# Sheet3.net
KiCad netlist of a schematic drawn in Altium Designer
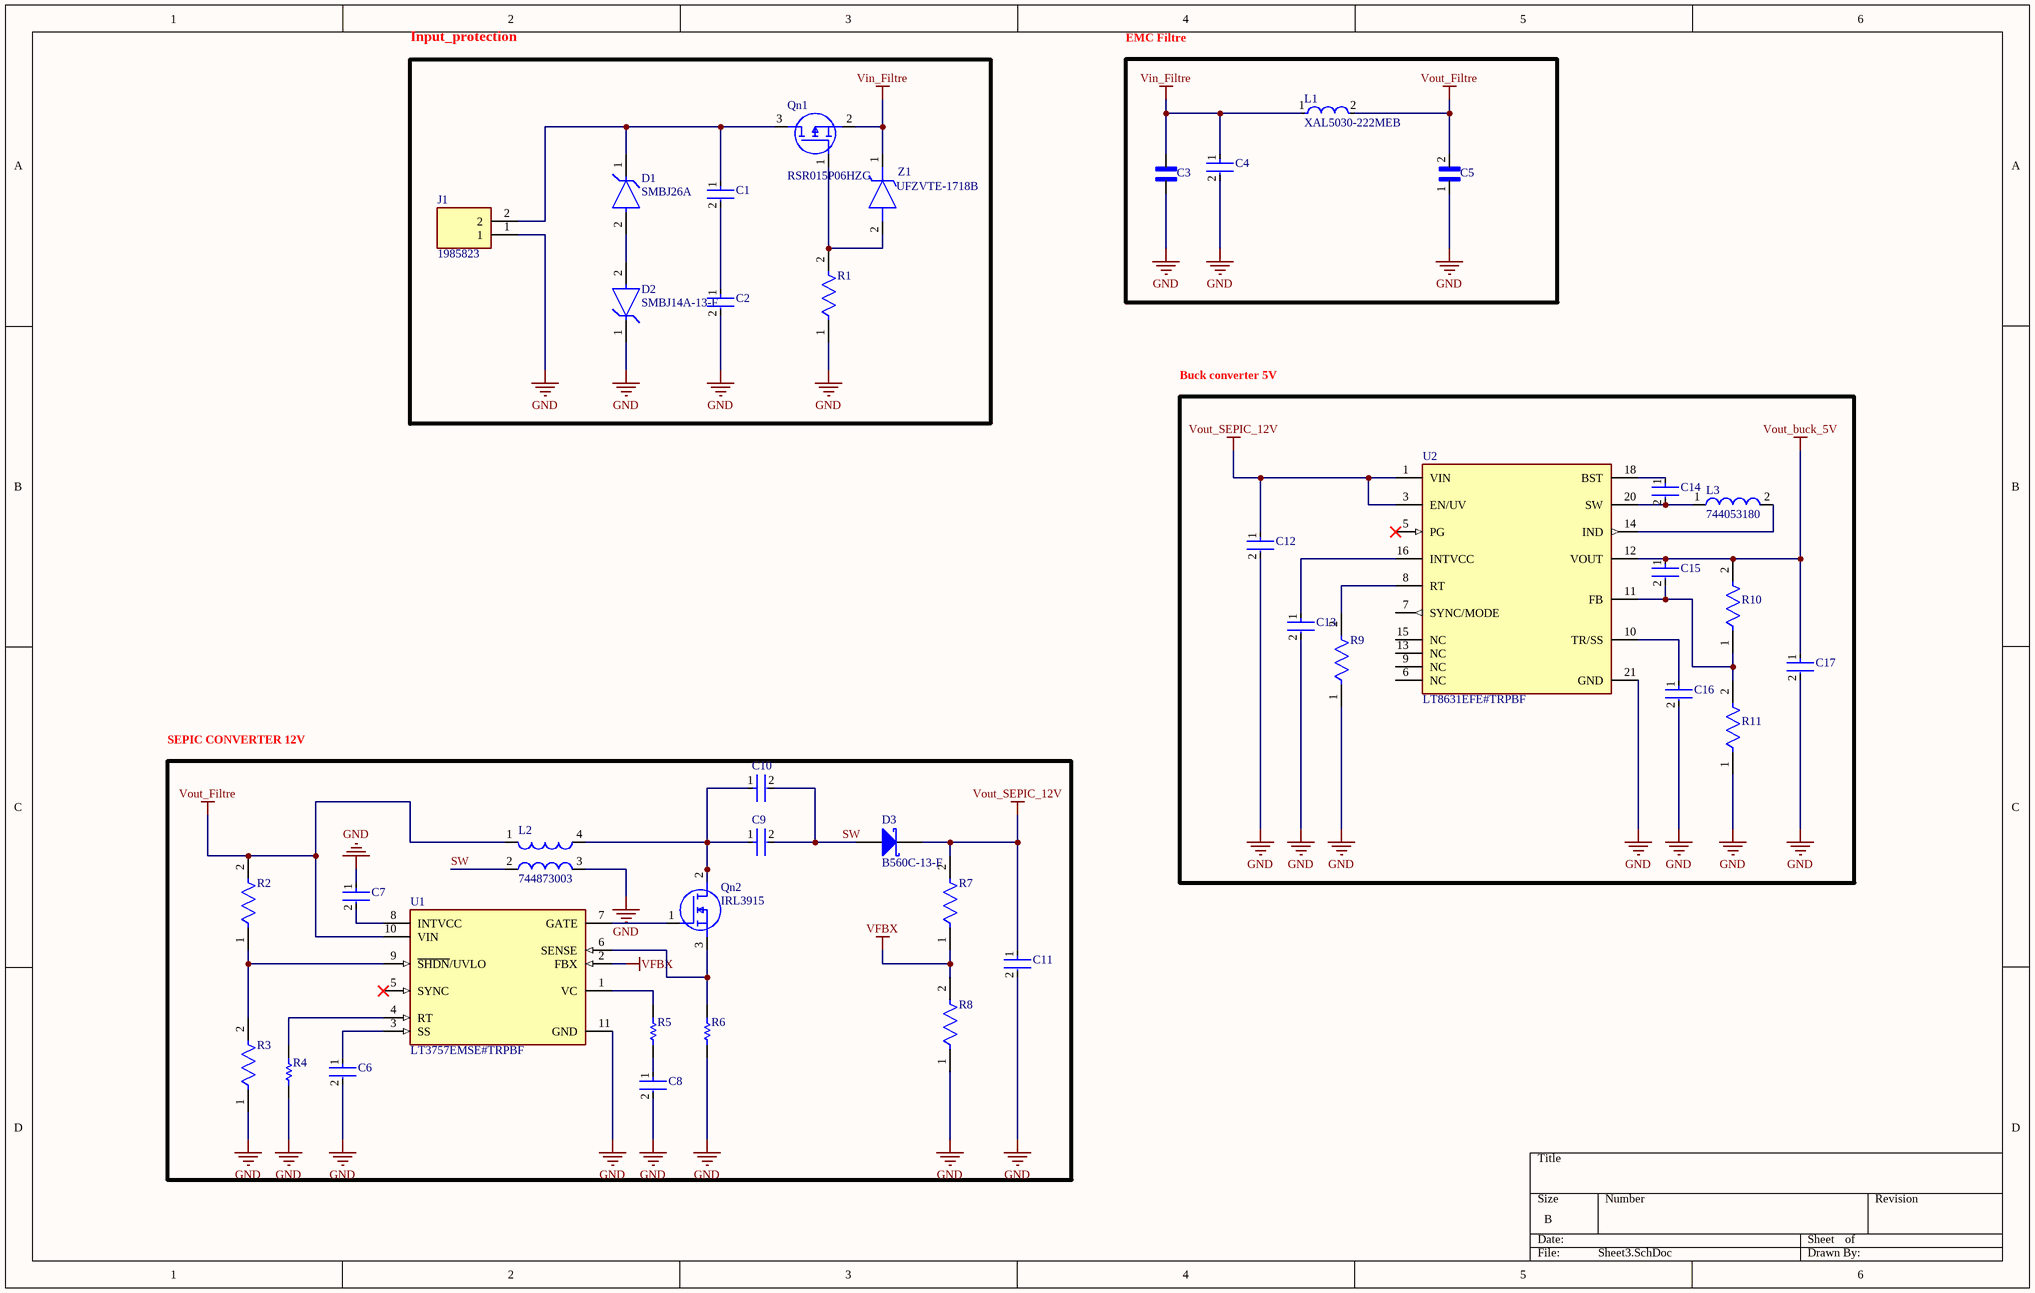
[diagram p0: Sheet3.SchDoc]

(export (version "E")
  (design (tool "Eeschema 10.0.6"))
  (components
    (comp (ref "C1")
      (value "CGA2B3X7R1H104M050BB")
      (footprint "FP-CGA2B-MFG")
      (description "Cap Ceramic 100nF 50V X7R 20% Pad SMD 0402 +125°C Automotive T/R")
      (fields (field (name "TOLERANCE") "20%"))
      (libsource (lib "Altium Content Vault") (part "b4654b650e69147ec39a6b967a45e02"))
    )
    (comp (ref "C2")
      (value "CGA2B3X7R1H104M050BB")
      (footprint "FP-CGA2B-MFG")
      (description "Cap Ceramic 100nF 50V X7R 20% Pad SMD 0402 +125°C Automotive T/R")
      (fields (field (name "TOLERANCE") "20%"))
      (libsource (lib "Altium Content Vault") (part "b4654b650e69147ec39a6b967a45e02"))
    )
    (comp (ref "C3")
      (value "CGA9N3X7R1H106K230KB")
      (footprint "CAP_CGA9N3X7R1H106K230KB")
      (description "10 ÂµF Â±10% 50V Ceramic Capacitor X7R 2220 (5750 Metric)")
      (fields (field (name "MF") "TDK"))
      (libsource (lib "CGA9N3X7R1H106K230KB") (part "CGA9N3X7R1H106K230KB"))
    )
    (comp (ref "C4")
      (value "C1210C225K5RACTU")
      (footprint "FP-C1210C225K5RACTU-MFG")
      (description "CAP CER 2.2UF 50V X7R 1210")
      (fields (field (name "TOLERANCE") "10%") (field (name "VOLTAGE") "100V"))
      (libsource (lib "Altium Content Vault") (part "b4654b650e69147ec39a6b967a45e02"))
    )
    (comp (ref "C5")
      (value "C3216X5R0J686M160AB")
      (footprint "CAPC3216X190N")
      (description "68 ÂµF Â±20% 6.3V Ceramic Capacitor X5R 1206 (3216 Metric)")
      (fields (field (name "MF") "TDK"))
      (libsource (lib "C3216X5R0J686M160AB") (part "C3216X5R0J686M160AB"))
    )
    (comp (ref "C6")
      (value "GRM1885C1H202JA01D")
      (footprint "FP-GRM188-0_1-e0_2_0_5-IPC_B")
      (description "Chip Multilayer Ceramic Capacitors for General Purpose, 0603, 2000pF, C0G, 30ppm/°C, 5%, 50V")
      (fields (field (name "TOLERANCE") "5%") (field (name "VOLTAGE") "50V"))
      (libsource (lib "Altium Content Vault") (part "11868f565c42a9108669ba33697ecf6"))
    )
    (comp (ref "C7")
      (value "GRM155R60J475ME47D")
      (footprint "FP-GRM155-0_1-IPC_B")
      (description "Chip Multilayer Ceramic Capacitors for General Purpose, 0402, 4.7uF, X5R, 15%, 20%, 6.3V")
      (fields (field (name "VOLTAGE") "6.3V") (field (name "TOLERANCE") "20%"))
      (libsource (lib "Altium Content Vault") (part "11868f565c42a9108669ba33697ecf6"))
    )
    (comp (ref "C8")
      (value "C1206C682K5RACTU")
      (footprint "FP-C1206C-EB-MFG")
      (description "CAP CER 6800PF 50V X7R 1206")
      (fields
        (field (name "OCTOPART") "https://octopart.com/c1206c682k5ractu-kemet-97937")
        (field (name "MANUFACTURER") "KEMET")
      )
      (libsource (lib "Altium Content Vault") (part "b4654b650e69147ec39a6b967a45e02"))
    )
    (comp (ref "C9")
      (value "GRM155R60J475ME47D")
      (footprint "FP-GRM155-0_1-IPC_B")
      (description "Chip Multilayer Ceramic Capacitors for General Purpose, 0402, 4.7uF, X5R, 15%, 20%, 6.3V")
      (fields (field (name "VOLTAGE") "6.3V") (field (name "TOLERANCE") "20%"))
      (libsource (lib "Altium Content Vault") (part "11868f565c42a9108669ba33697ecf6"))
    )
    (comp (ref "C10")
      (value "GRM155R60J475ME47D")
      (footprint "FP-GRM155-0_1-IPC_B")
      (description "Chip Multilayer Ceramic Capacitors for General Purpose, 0402, 4.7uF, X5R, 15%, 20%, 6.3V")
      (fields (field (name "VOLTAGE") "6.3V") (field (name "TOLERANCE") "20%"))
      (libsource (lib "Altium Content Vault") (part "11868f565c42a9108669ba33697ecf6"))
    )
    (comp (ref "C11")
      (value "C0805C476M9PACTU")
      (footprint "FP-C0805C476M9PACTU-MFG")
      (description "CAP CER 47UF 6.3V X5R 0805")
      (fields (field (name "VOLTAGE") "6.3V") (field (name "TOLERANCE") "20%"))
      (libsource (lib "Altium Content Vault") (part "11868f565c42a9108669ba33697ecf6"))
    )
    (comp (ref "C12")
      (value "C0805C106K8PACTU")
      (footprint "FP-C0805C-DG-MFG")
      (description "CAP CER 10UF 10V X5R 0805")
      (fields (field (name "TOLERANCE") "10%") (field (name "MANUFACTURER") "Kemet"))
      (libsource (lib "Altium Content Vault") (part "11868f565c42a9108669ba33697ecf6"))
    )
    (comp (ref "C13")
      (value "GRM188R71A225KE15D")
      (footprint "FP-GRM188-0_1-e0_2_0_5-MFG")
      (description "Chip Multilayer Ceramic Capacitors for General Purpose, 0603, 2.2uF, X7R, 15%, 10%, 10V")
      (fields (field (name "VOLTAGE") "10V") (field (name "TOLERANCE") "10%"))
      (libsource (lib "Altium Content Vault") (part "11868f565c42a9108669ba33697ecf6"))
    )
    (comp (ref "C14")
      (value "C0603C104K5RACTU")
      (footprint "FP-C0603C-CF-MFG")
      (description "CAP CER 0.1UF 50V X7R 0603")
      (fields (field (name "TOLERANCE") "0.1") (field (name "MANUFACTURER") "KEMET"))
      (libsource (lib "Altium Content Vault") (part "b4654b650e69147ec39a6b967a45e02"))
    )
    (comp (ref "C15")
      (value "C0402C479C5GACTU")
      (footprint "FP-C0402-BB-MFG")
      (description "CAP CER 4.7PF 50V NP0 0402")
      (fields
        (field (name "TOLERANCE") "0.25 pF")
        (field (name "OCTOPART") "https://octopart.com/c0402c479c5gactu-kemet-9144199")
      )
      (libsource (lib "Altium Content Vault") (part "b4654b650e69147ec39a6b967a45e02"))
    )
    (comp (ref "C16")
      (value "GRM1885C1H202JA01D")
      (footprint "FP-GRM188-0_1-e0_2_0_5-IPC_B")
      (description "Chip Multilayer Ceramic Capacitors for General Purpose, 0603, 2000pF, C0G, 30ppm/°C, 5%, 50V")
      (fields (field (name "TOLERANCE") "5%") (field (name "VOLTAGE") "50V"))
      (libsource (lib "Altium Content Vault") (part "11868f565c42a9108669ba33697ecf6"))
    )
    (comp (ref "C17")
      (value "GRM31CR60J476ME19L")
      (footprint "FP-GRM31C-0_2-e0_3_0_8-IPC_C")
      (description "Chip Multilayer Ceramic Capacitors for General Purpose, 1206, 47uF, X5R, 15%, 20%, 6.3V")
      (fields (field (name "TOLERANCE") "20%") (field (name "VOLTAGE") "6.3V"))
      (libsource (lib "Altium Content Vault") (part "02cd4be3c70576c341d710602a673aa"))
    )
    (comp (ref "D1")
      (value "SMBJ26A")
      (footprint "FP-SMBJ-MFG")
      (description "TVS DIODE 26V 42.1V DO214AA")
      (fields
        (field (name "MANUFACTURER") "Littelfuse")
        (field (name "OCTOPART") "https://octopart.com/smbj26a-littelfuse-350771")
      )
      (libsource (lib "Altium Content Vault") (part "f813f71cba58e380607f5dd3caf9714"))
    )
    (comp (ref "D2")
      (value "SMBJ14A-13-F")
      (footprint "FP-SMB-MFG")
      (description "TVS DIODE 14V 23.2V SMB")
      (libsource (lib "Altium Content Vault") (part "f813f71cba58e380607f5dd3caf9714"))
    )
    (comp (ref "D3")
      (value "B560C-13-F")
      (footprint "DIOD-B5X0C-2_M")
      (description "Schottky Barrier Rectifier, 5 A, 60 V, -55 to 125 degC, 2-Pin SMD, RoHS, Tape and Reel")
      (fields (field (name "MANUFACTURER") "DiodesIncorporated"))
      (libsource (lib "Altium Content Vault") (part "DSKY-KA-2"))
    )
    (comp (ref "J1")
      (value "1985823")
      (footprint "SamacSys:1985823")
      (description "Connector")
      (fields (field (name "MOUSER PART NUMBER") "651-1985823"))
      (libsource (lib "*") (part "1985823"))
    )
    (comp (ref "L1")
      (value "XAL5030-222MEB")
      (footprint "FP-XAL5030-222MEB-MFG")
      (description "Fixed Inductors 2.2uH 20% 9.7A 14.5mOhms")
      (fields (field (name "TOLERANCE") "20%"))
      (libsource (lib "Altium Content Vault") (part "725321dda6339637d4d059423bc1c3c"))
    )
    (comp (ref "L2")
      (value "744873003")
      (footprint "WE-DD-XL")
      (description "SMD Shielded Coupled Inductor WE-DD, L = 3.30 µH")
      (libsource (lib "Altium Content Vault") (part "PAS-IND-INDUCTOR-4J"))
    )
    (comp (ref "L3")
      (value "744053180")
      (footprint "WE-TPC-5828-LH")
      (description "SMD Shielded Tiny Power Inductor WE-TPC, L = 18.0 µH")
      (libsource (lib "Altium Content Vault") (part "PAS-IND-INDUCTOR-2"))
    )
    (comp (ref "Qn1")
      (value "RSR015P06HZG")
      (footprint "SamacSys:SOT95P280X90-3N")
      (description "MOSFET (P-Channel)")
      (libsource (lib "*") (part "RSR015P06HZG"))
    )
    (comp (ref "Qn2")
      (value "IRL3915")
      (footprint "SamacSys:TO254P469X1042X1930-3P")
      (description "MOSFET (N-Channel)")
      (fields
        (field (name "MANUFACTURER_PART_NUMBER") "IRL3705NPBF")
        (field (name "MOUSER PART NUMBER") "942-IRL3705NPBF")
      )
      (libsource (lib "*") (part "IRL3705NPBF"))
    )
    (comp (ref "R1")
      (value "CRCW040210K0FKEDC")
      (footprint "FP-CRCW0402-C-e3-IPC_C")
      (description "RES 10K OHM 1% 1/16W 0402")
      (fields (field (name "TOLERANCE") "1%"))
      (libsource (lib "Altium Content Vault") (part "1029c3af85768c4190bb7ad29bc67b5"))
    )
    (comp (ref "R2")
      (value "RMCF0603FG100K")
      (footprint "FP-RMCF0603-IPC_C")
      (description "100kΩ ±1% 0.1W 0603 Thick Film Chip Resistor AEC-Q200 compliant")
      (fields (field (name "TOLERANCE") "1%"))
      (libsource (lib "Altium Content Vault") (part "1029c3af85768c4190bb7ad29bc67b5"))
    )
    (comp (ref "R3")
      (value "CRCW080591K0FKEA")
      (footprint "FP-CRCW0805-e3-IPC_C")
      (description "RES Thick Film, 91kΩ, 1%, 0.125W, 100ppm/°C, 0805")
      (fields (field (name "TOLERANCE") "1%"))
      (libsource (lib "Altium Content Vault") (part "1029c3af85768c4190bb7ad29bc67b5"))
    )
    (comp (ref "R4")
      (value "CRCW040226K1FKED")
      (footprint "RESC1005X40X25LL05T05")
      (fields (field (name "MANUFACTURER") "Vishay Dale"))
      (libsource (lib "Altium Content Vault") (part "RES"))
    )
    (comp (ref "R5")
      (value "CRCW040210K0FKEDHP")
      (footprint "RESC1005X40X25ML05T10")
      (fields (field (name "MANUFACTURER") "Vishay Dale"))
      (libsource (lib "Altium Content Vault") (part "RES"))
    )
    (comp (ref "R6")
      (value "WSL12068L000FEA")
      (footprint "RESC3216X89X51LL25T25")
      (fields (field (name "MANUFACTURER") "Vishay Dale"))
      (libsource (lib "Altium Content Vault") (part "RES"))
    )
    (comp (ref "R7")
      (value "RC0603FR-07105KL")
      (footprint "FP-RC0603-0_55-IPC_B")
      (description "RES SMD 105K OHM 1% 1/10W 0603")
      (fields (field (name "TOLERANCE") "1%"))
      (libsource (lib "Altium Content Vault") (part "1029c3af85768c4190bb7ad29bc67b5"))
    )
    (comp (ref "R8")
      (value "RG1005N-1582-B-T5")
      (footprint "FP-RG1005-IPC_A")
      (description "Automotive Metal Thin Film Chip Resistor, 0402, 15.8kΩ, 0.1%, 10ppm/°C, 0.0625W, 75V")
      (fields (field (name "TOLERANCE") "0.1%"))
      (libsource (lib "Altium Content Vault") (part "1029c3af85768c4190bb7ad29bc67b5"))
    )
    (comp (ref "R9")
      (value "CRCW080519K6FKEA")
      (footprint "FP-CRCW0805-e3-IPC_C")
      (description "RES Thick Film, 19.6kΩ, 1%, 0.125W, 100ppm/°C, 0805")
      (fields (field (name "TOLERANCE") "1%"))
      (libsource (lib "Altium Content Vault") (part "1029c3af85768c4190bb7ad29bc67b5"))
    )
    (comp (ref "R10")
      (value "RMCF0603JT1M00")
      (footprint "FP-RMCF0603-IPC_B")
      (description "1MΩ ±5% 0.1W 0603 Thick Film Chip Resistor AEC-Q200 compliant")
      (fields (field (name "TOLERANCE") "5%"))
      (libsource (lib "Altium Content Vault") (part "1029c3af85768c4190bb7ad29bc67b5"))
    )
    (comp (ref "R11")
      (value "RG3216N-1913-B-T5")
      (footprint "FP-RG3216-IPC_A")
      (description "Automotive Metal Thin Film Chip Resistor, 1206, 191kΩ, 0.1%, 10ppm/°C, 0.25W, 200V")
      (fields (field (name "TOLERANCE") "0.1%"))
      (libsource (lib "Altium Content Vault") (part "1029c3af85768c4190bb7ad29bc67b5"))
    )
    (comp (ref "U1")
      (value "LT3757EMSE#TRPBF")
      (footprint "FP-MSE-10-05-08-1664-IPC_C")
      (description "IC REG CTRLR MULT TOP 10MSOP")
      (libsource (lib "Altium Content Vault") (part "ab01c58094b4079bf20d0d029cd08cd"))
    )
    (comp (ref "U2")
      (value "LT8631EFE#TRPBF")
      (footprint "FP-FE-20_16_-05-08-1924-C-MFG")
      (description "IC REG BUCK ADJ 1A 20TSSOP")
      (libsource (lib "Altium Content Vault") (part "009895d8221129b75cb09bd5e43c4ac"))
    )
    (comp (ref "Z1")
      (value "UFZVTE-1718B")
      (footprint "SamacSys:SODFL2512X90N")
      (description "Zener Diode")
      (libsource (lib "*") (part "UFZVTE-1718B"))
    )
  )
  (nets
    (net (code "1") (name "/SW") (class "Default")
      (node (ref "C10") (pin "2") (pinfunction "2_2") (pintype "passive"))
      (node (ref "C9") (pin "2") (pinfunction "2_2") (pintype "passive"))
      (node (ref "D3") (pin "2") (pinfunction "A_2") (pintype "passive"))
      (node (ref "L2") (pin "2") (pinfunction "2_2") (pintype "passive"))
    )
    (net (code "2") (name "GND") (class "Default")
      (node (ref "C11") (pin "2") (pinfunction "2_2") (pintype "passive"))
      (node (ref "C12") (pin "2") (pinfunction "2_2") (pintype "passive"))
      (node (ref "C13") (pin "2") (pinfunction "2_2") (pintype "passive"))
      (node (ref "C16") (pin "2") (pinfunction "2_2") (pintype "passive"))
      (node (ref "C17") (pin "2") (pinfunction "2_2") (pintype "passive"))
      (node (ref "C2") (pin "2") (pinfunction "2_2") (pintype "passive"))
      (node (ref "C3") (pin "1") (pinfunction "1_1") (pintype "passive"))
      (node (ref "C4") (pin "2") (pinfunction "2_2") (pintype "passive"))
      (node (ref "C5") (pin "1") (pinfunction "1_1") (pintype "passive"))
      (node (ref "C6") (pin "2") (pinfunction "2_2") (pintype "passive"))
      (node (ref "C7") (pin "1") (pinfunction "1_1") (pintype "passive"))
      (node (ref "C8") (pin "2") (pinfunction "2_2") (pintype "passive"))
      (node (ref "D2") (pin "1") (pinfunction "C_1") (pintype "passive"))
      (node (ref "J1") (pin "1") (pinfunction "1_1") (pintype "passive"))
      (node (ref "L2") (pin "3") (pinfunction "3_3") (pintype "passive"))
      (node (ref "R1") (pin "1") (pinfunction "1_1") (pintype "passive"))
      (node (ref "R11") (pin "1") (pinfunction "1_1") (pintype "passive"))
      (node (ref "R3") (pin "1") (pinfunction "1_1") (pintype "passive"))
      (node (ref "R4") (pin "1") (pinfunction "1_1") (pintype "passive"))
      (node (ref "R6") (pin "1") (pinfunction "1_1") (pintype "passive"))
      (node (ref "R8") (pin "1") (pinfunction "1_1") (pintype "passive"))
      (node (ref "R9") (pin "1") (pinfunction "1_1") (pintype "passive"))
      (node (ref "U1") (pin "11") (pinfunction "GND_11") (pintype "power_in"))
      (node (ref "U2") (pin "21") (pinfunction "GND_21") (pintype "passive"))
    )
    (net (code "3") (name "Net-(C1-Pad2)") (class "Default")
      (node (ref "C1") (pin "2") (pinfunction "2_2") (pintype "passive"))
      (node (ref "C2") (pin "1") (pinfunction "1_1") (pintype "passive"))
    )
    (net (code "4") (name "Net-(C8-Pad1)") (class "Default")
      (node (ref "C8") (pin "1") (pinfunction "1_1") (pintype "passive"))
      (node (ref "R5") (pin "1") (pinfunction "1_1") (pintype "passive"))
    )
    (net (code "5") (name "Net-(D1-A)") (class "Default")
      (node (ref "D1") (pin "2") (pinfunction "A_2") (pintype "passive"))
      (node (ref "D2") (pin "2") (pinfunction "A_2") (pintype "passive"))
    )
    (net (code "6") (name "Net-(D1-C)") (class "Default")
      (node (ref "C1") (pin "1") (pinfunction "1_1") (pintype "passive"))
      (node (ref "D1") (pin "1") (pinfunction "C_1") (pintype "passive"))
      (node (ref "J1") (pin "2") (pinfunction "2_2") (pintype "passive"))
      (node (ref "Qn1") (pin "3") (pinfunction "D_3") (pintype "passive"))
    )
    (net (code "7") (name "Net-(Qn1-G)") (class "Default")
      (node (ref "Qn1") (pin "1") (pinfunction "G_1") (pintype "passive"))
      (node (ref "R1") (pin "2") (pinfunction "2_2") (pintype "passive"))
      (node (ref "Z1") (pin "2") (pinfunction "A_2") (pintype "passive"))
    )
    (net (code "8") (name "Net-(Qn2-D)") (class "Default")
      (node (ref "C10") (pin "1") (pinfunction "1_1") (pintype "passive"))
      (node (ref "C9") (pin "1") (pinfunction "1_1") (pintype "passive"))
      (node (ref "L2") (pin "4") (pinfunction "4_4") (pintype "passive"))
      (node (ref "Qn2") (pin "2") (pinfunction "D_2") (pintype "passive"))
    )
    (net (code "9") (name "Net-(Qn2-G)") (class "Default")
      (node (ref "Qn2") (pin "1") (pinfunction "G_1") (pintype "passive"))
      (node (ref "U1") (pin "7") (pinfunction "GATE_7") (pintype "passive"))
    )
    (net (code "10") (name "Net-(Qn2-S)") (class "Default")
      (node (ref "Qn2") (pin "3") (pinfunction "S_3") (pintype "passive"))
      (node (ref "R6") (pin "2") (pinfunction "2_2") (pintype "passive"))
      (node (ref "U1") (pin "6") (pinfunction "SENSE_6") (pintype "input"))
    )
    (net (code "11") (name "Net-(U1-INTVCC)") (class "Default")
      (node (ref "C7") (pin "2") (pinfunction "2_2") (pintype "passive"))
      (node (ref "U1") (pin "8") (pinfunction "INTVCC_8") (pintype "power_in"))
    )
    (net (code "12") (name "Net-(U1-RT)") (class "Default")
      (node (ref "R4") (pin "2") (pinfunction "2_2") (pintype "passive"))
      (node (ref "U1") (pin "4") (pinfunction "RT_4") (pintype "input"))
    )
    (net (code "13") (name "Net-(U1-SS)") (class "Default")
      (node (ref "C6") (pin "1") (pinfunction "1_1") (pintype "passive"))
      (node (ref "U1") (pin "3") (pinfunction "SS_3") (pintype "input"))
    )
    (net (code "14") (name "Net-(U1-VC)") (class "Default")
      (node (ref "R5") (pin "2") (pinfunction "2_2") (pintype "passive"))
      (node (ref "U1") (pin "1") (pinfunction "VC_1") (pintype "passive"))
    )
    (net (code "15") (name "Net-(U1-~{SHDN}{slash}UVLO)") (class "Default")
      (node (ref "R2") (pin "1") (pinfunction "1_1") (pintype "passive"))
      (node (ref "R3") (pin "2") (pinfunction "2_2") (pintype "passive"))
      (node (ref "U1") (pin "9") (pinfunction "~{SHDN}/UVLO_9") (pintype "input"))
    )
    (net (code "16") (name "Net-(U2-BST)") (class "Default")
      (node (ref "C14") (pin "1") (pinfunction "1_1") (pintype "passive"))
      (node (ref "U2") (pin "18") (pinfunction "BST_18") (pintype "passive"))
    )
    (net (code "17") (name "Net-(U2-FB)") (class "Default")
      (node (ref "C15") (pin "2") (pinfunction "2_2") (pintype "passive"))
      (node (ref "R10") (pin "1") (pinfunction "1_1") (pintype "passive"))
      (node (ref "R11") (pin "2") (pinfunction "2_2") (pintype "passive"))
      (node (ref "U2") (pin "11") (pinfunction "FB_11") (pintype "passive"))
    )
    (net (code "18") (name "Net-(U2-IND)") (class "Default")
      (node (ref "L3") (pin "2") (pinfunction "2_2") (pintype "passive"))
      (node (ref "U2") (pin "14") (pinfunction "IND_14") (pintype "output"))
    )
    (net (code "19") (name "Net-(U2-INTVCC)") (class "Default")
      (node (ref "C13") (pin "1") (pinfunction "1_1") (pintype "passive"))
      (node (ref "U2") (pin "16") (pinfunction "INTVCC_16") (pintype "passive"))
    )
    (net (code "20") (name "Net-(U2-RT)") (class "Default")
      (node (ref "R9") (pin "2") (pinfunction "2_2") (pintype "passive"))
      (node (ref "U2") (pin "8") (pinfunction "RT_8") (pintype "passive"))
    )
    (net (code "21") (name "Net-(U2-SW)") (class "Default")
      (node (ref "C14") (pin "2") (pinfunction "2_2") (pintype "passive"))
      (node (ref "L3") (pin "1") (pinfunction "1_1") (pintype "passive"))
      (node (ref "U2") (pin "20") (pinfunction "SW_20") (pintype "passive"))
    )
    (net (code "22") (name "Net-(U2-TR{slash}SS)") (class "Default")
      (node (ref "C16") (pin "1") (pinfunction "1_1") (pintype "passive"))
      (node (ref "U2") (pin "10") (pinfunction "TR/SS_10") (pintype "passive"))
    )
    (net (code "23") (name "VFBX") (class "Default")
      (node (ref "R7") (pin "1") (pinfunction "1_1") (pintype "passive"))
      (node (ref "R8") (pin "2") (pinfunction "2_2") (pintype "passive"))
      (node (ref "U1") (pin "2") (pinfunction "FBX_2") (pintype "input"))
    )
    (net (code "24") (name "Vin_Filtre") (class "Default")
      (node (ref "C3") (pin "2") (pinfunction "2_2") (pintype "passive"))
      (node (ref "C4") (pin "1") (pinfunction "1_1") (pintype "passive"))
      (node (ref "L1") (pin "1") (pinfunction "1_1") (pintype "passive"))
      (node (ref "Qn1") (pin "2") (pinfunction "S_2") (pintype "passive"))
      (node (ref "Z1") (pin "1") (pinfunction "K_1") (pintype "passive"))
    )
    (net (code "25") (name "Vout_Filtre") (class "Default")
      (node (ref "C5") (pin "2") (pinfunction "2_2") (pintype "passive"))
      (node (ref "L1") (pin "2") (pinfunction "2_2") (pintype "passive"))
      (node (ref "L2") (pin "1") (pinfunction "1_1") (pintype "passive"))
      (node (ref "R2") (pin "2") (pinfunction "2_2") (pintype "passive"))
      (node (ref "U1") (pin "10") (pinfunction "VIN_10") (pintype "power_in"))
    )
    (net (code "26") (name "Vout_SEPIC_12V") (class "Default")
      (node (ref "C11") (pin "1") (pinfunction "1_1") (pintype "passive"))
      (node (ref "C12") (pin "1") (pinfunction "1_1") (pintype "passive"))
      (node (ref "D3") (pin "1") (pinfunction "K_1") (pintype "passive"))
      (node (ref "R7") (pin "2") (pinfunction "2_2") (pintype "passive"))
      (node (ref "U2") (pin "1") (pinfunction "VIN_1") (pintype "power_in"))
      (node (ref "U2") (pin "3") (pinfunction "EN/UV_3") (pintype "passive"))
    )
    (net (code "27") (name "Vout_buck_5V") (class "Default")
      (node (ref "C15") (pin "1") (pinfunction "1_1") (pintype "passive"))
      (node (ref "C17") (pin "1") (pinfunction "1_1") (pintype "passive"))
      (node (ref "R10") (pin "2") (pinfunction "2_2") (pintype "passive"))
      (node (ref "U2") (pin "12") (pinfunction "VOUT_12") (pintype "passive"))
    )
    (net (code "28") (name "unconnected-(U1-SYNC-Pad5)") (class "Default")
      (node (ref "U1") (pin "5") (pinfunction "SYNC_5") (pintype "input+no_connect"))
    )
    (net (code "29") (name "unconnected-(U2-NC-Pad6)") (class "Default")
      (node (ref "U2") (pin "6") (pinfunction "NC_6") (pintype "passive"))
    )
    (net (code "30") (name "unconnected-(U2-NC-Pad9)") (class "Default")
      (node (ref "U2") (pin "9") (pinfunction "NC_9") (pintype "passive"))
    )
    (net (code "31") (name "unconnected-(U2-NC-Pad13)") (class "Default")
      (node (ref "U2") (pin "13") (pinfunction "NC_13") (pintype "passive"))
    )
    (net (code "32") (name "unconnected-(U2-NC-Pad15)") (class "Default")
      (node (ref "U2") (pin "15") (pinfunction "NC_15") (pintype "passive"))
    )
    (net (code "33") (name "unconnected-(U2-PG-Pad5)") (class "Default")
      (node (ref "U2") (pin "5") (pinfunction "PG_5") (pintype "input+no_connect"))
    )
    (net (code "34") (name "unconnected-(U2-SYNC{slash}MODE-Pad7)") (class "Default")
      (node (ref "U2") (pin "7") (pinfunction "SYNC/MODE_7") (pintype "output"))
    )
  )
)
